# blinky.net
KiCad netlist of a schematic drawn in EAGLE
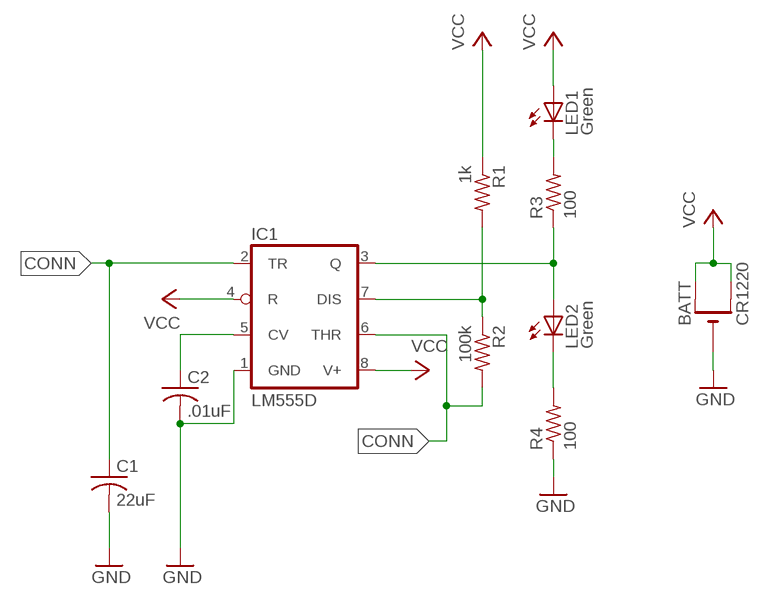
[diagram p0: schematic, sheet 1]

(export (version "E")
  (design (tool "Eeschema 10.0.6"))
  (components
    (comp (ref "BATT")
      (value "CR1220")
      (footprint "eagle-import:CR1220-SMD")
      (libsource (lib "eagle-import") (part "CR1220SMT"))
    )
    (comp (ref "C1")
      (value "22uF")
      (footprint "eagle-import:C0805")
      (fields (field (name "MPN") "LMK212BJ226MG-T"))
      (libsource (lib "eagle-import") (part "C-USC0805"))
    )
    (comp (ref "C2")
      (value ".01uF")
      (footprint "eagle-import:C0805")
      (fields (field (name "MF") "AVX CORPORATION") (field (name "MPN") "08051C103K4T2A"))
      (libsource (lib "eagle-import") (part "C-USC0805"))
    )
    (comp (ref "IC1")
      (value "LM555D")
      (footprint "eagle-import:SO08")
      (fields (field (name "MPN") "1022"))
      (libsource (lib "eagle-import") (part "555DLM"))
    )
    (comp (ref "LED1")
      (value "Green")
      (footprint "eagle-import:CHIP-LED0805")
      (fields (field (name "MPN") "MCL-S270GC"))
      (libsource (lib "eagle-import") (part "LEDCHIP-LED0805"))
    )
    (comp (ref "LED2")
      (value "Green")
      (footprint "eagle-import:CHIP-LED0805")
      (fields (field (name "MPN") "MCL-S270GC"))
      (libsource (lib "eagle-import") (part "LEDCHIP-LED0805"))
    )
    (comp (ref "R1")
      (value "1k")
      (footprint "eagle-import:R0805")
      (fields (field (name "MF") "VISHAY/DALE") (field (name "MPN") "CRCW08051K00FKTA"))
      (libsource (lib "eagle-import") (part "R-US_R0805"))
    )
    (comp (ref "R2")
      (value "100k")
      (footprint "eagle-import:R0805")
      (fields (field (name "MPN") "RN73C2A100KBTG"))
      (libsource (lib "eagle-import") (part "R-US_R0805"))
    )
    (comp (ref "R3")
      (value "100")
      (footprint "eagle-import:R0805")
      (fields (field (name "MF") "VISHAY/DALE") (field (name "MPN") "CRCW0805100RFKTA"))
      (libsource (lib "eagle-import") (part "R-US_R0805"))
    )
    (comp (ref "R4")
      (value "100")
      (footprint "eagle-import:R0805")
      (fields (field (name "MF") "VISHAY/DALE") (field (name "MPN") "CRCW0805100RFKTA"))
      (libsource (lib "eagle-import") (part "R-US_R0805"))
    )
  )
  (nets
    (net (code "1") (name "CONN") (class "Default")
      (node (ref "C1") (pin "1") (pinfunction "1_1") (pintype "passive"))
      (node (ref "IC1") (pin "2") (pinfunction "TR_2") (pintype "input"))
      (node (ref "IC1") (pin "6") (pinfunction "THR_6") (pintype "input"))
      (node (ref "R2") (pin "2") (pinfunction "2_2") (pintype "passive"))
    )
    (net (code "2") (name "GND") (class "Default")
      (node (ref "BATT") (pin "-") (pinfunction "-_-") (pintype "passive"))
      (node (ref "C1") (pin "2") (pinfunction "2_2") (pintype "passive"))
      (node (ref "C2") (pin "2") (pinfunction "2_2") (pintype "passive"))
      (node (ref "IC1") (pin "1") (pinfunction "GND_1") (pintype "power_in"))
      (node (ref "R4") (pin "1") (pinfunction "1_1") (pintype "passive"))
    )
    (net (code "3") (name "Net-(IC1-CV)") (class "Default")
      (node (ref "C2") (pin "1") (pinfunction "1_1") (pintype "passive"))
      (node (ref "IC1") (pin "5") (pinfunction "CV_5") (pintype "input"))
    )
    (net (code "4") (name "Net-(IC1-DIS)") (class "Default")
      (node (ref "IC1") (pin "7") (pinfunction "DIS_7") (pintype "input"))
      (node (ref "R1") (pin "2") (pinfunction "2_2") (pintype "passive"))
      (node (ref "R2") (pin "1") (pinfunction "1_1") (pintype "passive"))
    )
    (net (code "5") (name "Net-(IC1-Q)") (class "Default")
      (node (ref "IC1") (pin "3") (pinfunction "Q_3") (pintype "output"))
      (node (ref "LED2") (pin "A") (pinfunction "A_A") (pintype "passive"))
      (node (ref "R3") (pin "1") (pinfunction "1_1") (pintype "passive"))
    )
    (net (code "6") (name "Net-(LED1-PadC)") (class "Default")
      (node (ref "LED1") (pin "C") (pinfunction "C_C") (pintype "passive"))
      (node (ref "R3") (pin "2") (pinfunction "2_2") (pintype "passive"))
    )
    (net (code "7") (name "Net-(LED2-PadC)") (class "Default")
      (node (ref "LED2") (pin "C") (pinfunction "C_C") (pintype "passive"))
      (node (ref "R4") (pin "2") (pinfunction "2_2") (pintype "passive"))
    )
    (net (code "8") (name "VCC") (class "Default")
      (node (ref "BATT") (pin "+$1") (pinfunction "+_+$1") (pintype "passive"))
      (node (ref "BATT") (pin "+$2") (pinfunction "+1_+$2") (pintype "passive"))
      (node (ref "IC1") (pin "4") (pinfunction "R_4") (pintype "input"))
      (node (ref "IC1") (pin "8") (pinfunction "V+_8") (pintype "power_in"))
      (node (ref "LED1") (pin "A") (pinfunction "A_A") (pintype "passive"))
      (node (ref "R1") (pin "1") (pinfunction "1_1") (pintype "passive"))
    )
  )
)
